# mem.net
KiCad netlist of a schematic drawn in Altium Designer
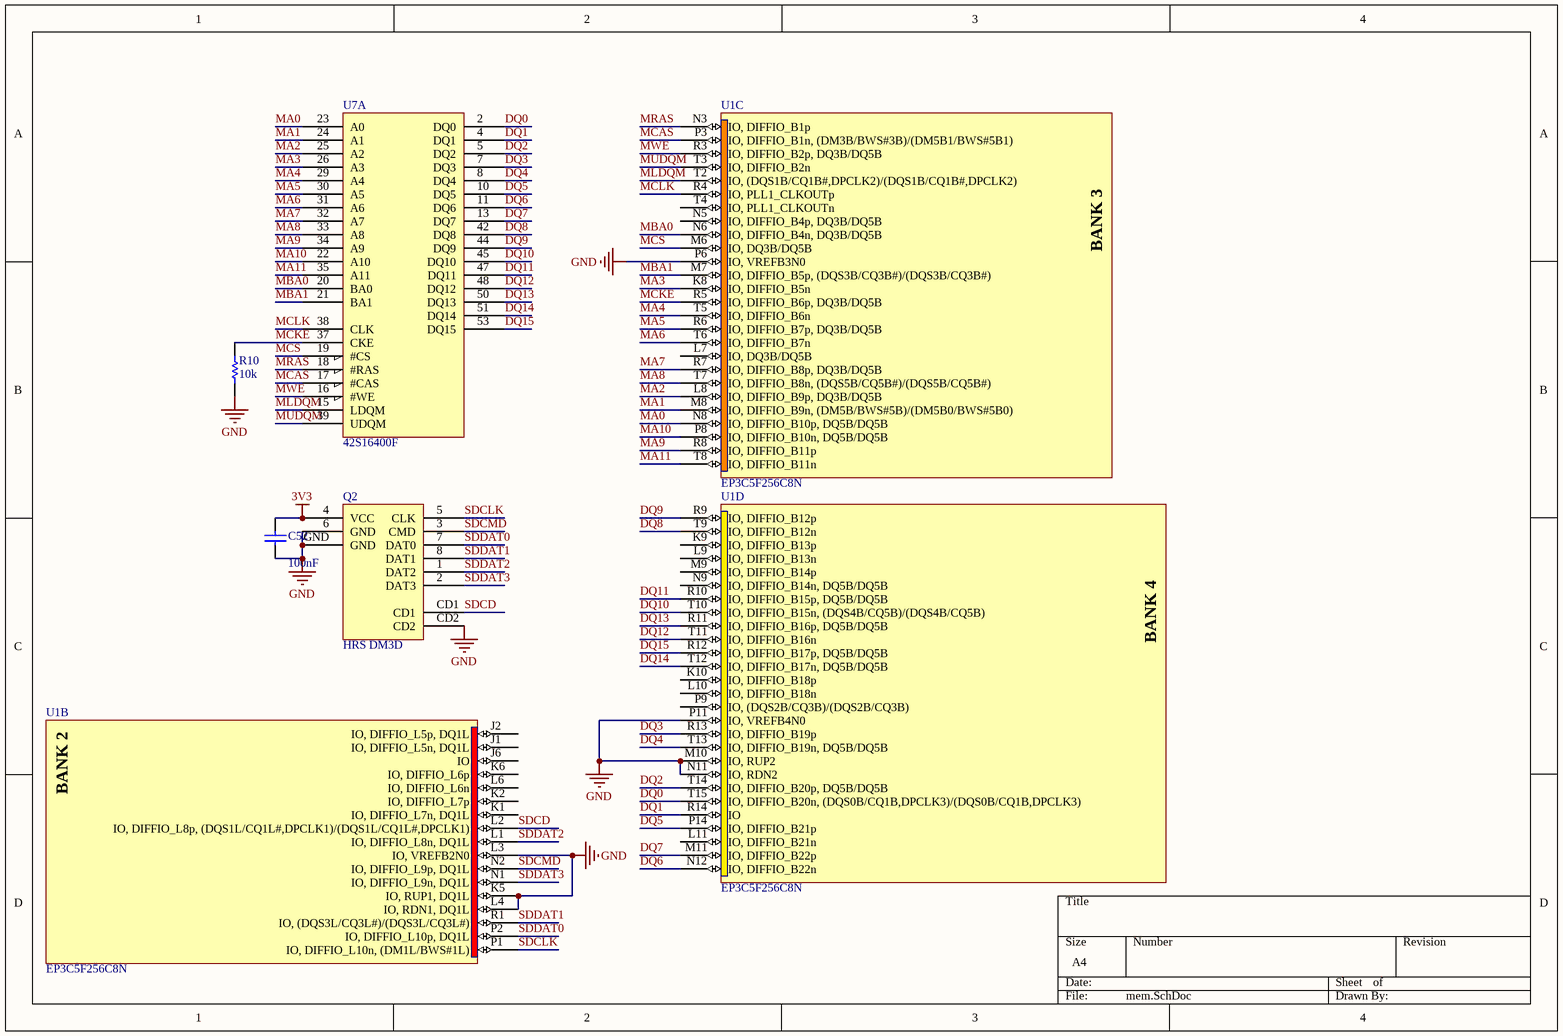
[diagram p0: mem.SchDoc]

(export (version "E")
  (design (tool "Eeschema 10.0.6"))
  (components
    (comp (ref "C52")
      (value "100nF")
      (footprint "CAPC1005X06L")
      (description "Capacitor")
      (fields (field (name "PUBLISHER") "Altium Limited"))
      (libsource (lib "Miscellaneous Devices") (part "Cap"))
    )
    (comp (ref "Q2") (value "HRS DM3D") (footprint "HRS DM3D") (libsource (lib "parts") (part "HRS DM3D")))
    (comp (ref "R10")
      (value "10k")
      (footprint "CAPC2012X135N")
      (description "Resistor")
      (fields (field (name "Comment") "Res1") (field (name "PUBLISHER") "Altium Limited"))
      (libsource (lib "Miscellaneous Devices") (part "Res1"))
    )
    (comp (ref "U1")
      (value "EP3C5F256C8N")
      (footprint "FBGA256-2")
      (fields (field (name "PUBLISHER") "Altium Limited"))
      (libsource (lib "Altera Cyclone III") (part "EP3C5F256C8N"))
    )
    (comp (ref "U7")
      (value "42S16400F")
      (footprint "54_TSOP2_400AF_N")
      (libsource (lib "parts") (part "45S16400F"))
    )
  )
  (nets
    (net (code "1") (name "/DQ0") (class "Default")
      (node (ref "U1") (pin "T15") (pinfunction "IO,_DIFFIO_B20n,_(DQS0B/CQ1B,DPCLK3)/(DQS0B/CQ1B,DPCLK3)_T15") (pintype "bidirectional"))
      (node (ref "U7") (pin "2") (pinfunction "DQ0_2") (pintype "passive"))
    )
    (net (code "2") (name "/DQ1") (class "Default")
      (node (ref "U1") (pin "R14") (pinfunction "IO_R14") (pintype "bidirectional"))
      (node (ref "U7") (pin "4") (pinfunction "DQ1_4") (pintype "passive"))
    )
    (net (code "3") (name "/DQ2") (class "Default")
      (node (ref "U1") (pin "T14") (pinfunction "IO,_DIFFIO_B20p,_DQ5B/DQ5B_T14") (pintype "bidirectional"))
      (node (ref "U7") (pin "5") (pinfunction "DQ2_5") (pintype "passive"))
    )
    (net (code "4") (name "/DQ3") (class "Default")
      (node (ref "U1") (pin "R13") (pinfunction "IO,_DIFFIO_B19p_R13") (pintype "bidirectional"))
      (node (ref "U7") (pin "7") (pinfunction "DQ3_7") (pintype "passive"))
    )
    (net (code "5") (name "/DQ4") (class "Default")
      (node (ref "U1") (pin "T13") (pinfunction "IO,_DIFFIO_B19n,_DQ5B/DQ5B_T13") (pintype "bidirectional"))
      (node (ref "U7") (pin "8") (pinfunction "DQ4_8") (pintype "passive"))
    )
    (net (code "6") (name "/DQ5") (class "Default")
      (node (ref "U1") (pin "P14") (pinfunction "IO,_DIFFIO_B21p_P14") (pintype "bidirectional"))
      (node (ref "U7") (pin "10") (pinfunction "DQ5_10") (pintype "passive"))
    )
    (net (code "7") (name "/DQ6") (class "Default")
      (node (ref "U1") (pin "N12") (pinfunction "IO,_DIFFIO_B22n_N12") (pintype "bidirectional"))
      (node (ref "U7") (pin "11") (pinfunction "DQ6_11") (pintype "passive"))
    )
    (net (code "8") (name "/DQ7") (class "Default")
      (node (ref "U1") (pin "M11") (pinfunction "IO,_DIFFIO_B22p_M11") (pintype "bidirectional"))
      (node (ref "U7") (pin "13") (pinfunction "DQ7_13") (pintype "passive"))
    )
    (net (code "9") (name "/DQ8") (class "Default")
      (node (ref "U1") (pin "T9") (pinfunction "IO,_DIFFIO_B12n_T9") (pintype "bidirectional"))
      (node (ref "U7") (pin "42") (pinfunction "DQ8_42") (pintype "passive"))
    )
    (net (code "10") (name "/DQ9") (class "Default")
      (node (ref "U1") (pin "R9") (pinfunction "IO,_DIFFIO_B12p_R9") (pintype "bidirectional"))
      (node (ref "U7") (pin "44") (pinfunction "DQ9_44") (pintype "passive"))
    )
    (net (code "11") (name "/DQ10") (class "Default")
      (node (ref "U1") (pin "T10") (pinfunction "IO,_DIFFIO_B15n,_(DQS4B/CQ5B)/(DQS4B/CQ5B)_T10") (pintype "bidirectional"))
      (node (ref "U7") (pin "45") (pinfunction "DQ10_45") (pintype "passive"))
    )
    (net (code "12") (name "/DQ11") (class "Default")
      (node (ref "U1") (pin "R10") (pinfunction "IO,_DIFFIO_B15p,_DQ5B/DQ5B_R10") (pintype "bidirectional"))
      (node (ref "U7") (pin "47") (pinfunction "DQ11_47") (pintype "passive"))
    )
    (net (code "13") (name "/DQ12") (class "Default")
      (node (ref "U1") (pin "T11") (pinfunction "IO,_DIFFIO_B16n_T11") (pintype "bidirectional"))
      (node (ref "U7") (pin "48") (pinfunction "DQ12_48") (pintype "passive"))
    )
    (net (code "14") (name "/DQ13") (class "Default")
      (node (ref "U1") (pin "R11") (pinfunction "IO,_DIFFIO_B16p,_DQ5B/DQ5B_R11") (pintype "bidirectional"))
      (node (ref "U7") (pin "50") (pinfunction "DQ13_50") (pintype "passive"))
    )
    (net (code "15") (name "/DQ14") (class "Default")
      (node (ref "U1") (pin "T12") (pinfunction "IO,_DIFFIO_B17n,_DQ5B/DQ5B_T12") (pintype "bidirectional"))
      (node (ref "U7") (pin "51") (pinfunction "DQ14_51") (pintype "passive"))
    )
    (net (code "16") (name "/DQ15") (class "Default")
      (node (ref "U1") (pin "R12") (pinfunction "IO,_DIFFIO_B17p,_DQ5B/DQ5B_R12") (pintype "bidirectional"))
      (node (ref "U7") (pin "53") (pinfunction "DQ15_53") (pintype "passive"))
    )
    (net (code "17") (name "/MA0") (class "Default")
      (node (ref "U1") (pin "N8") (pinfunction "IO,_DIFFIO_B10p,_DQ5B/DQ5B_N8") (pintype "bidirectional"))
      (node (ref "U7") (pin "23") (pinfunction "A0_23") (pintype "passive"))
    )
    (net (code "18") (name "/MA1") (class "Default")
      (node (ref "U1") (pin "M8") (pinfunction "IO,_DIFFIO_B9n,_(DM5B/BWS#5B)/(DM5B0/BWS#5B0)_M8") (pintype "bidirectional"))
      (node (ref "U7") (pin "24") (pinfunction "A1_24") (pintype "passive"))
    )
    (net (code "19") (name "/MA2") (class "Default")
      (node (ref "U1") (pin "L8") (pinfunction "IO,_DIFFIO_B9p,_DQ3B/DQ5B_L8") (pintype "bidirectional"))
      (node (ref "U7") (pin "25") (pinfunction "A2_25") (pintype "passive"))
    )
    (net (code "20") (name "/MA3") (class "Default")
      (node (ref "U1") (pin "K8") (pinfunction "IO,_DIFFIO_B5n_K8") (pintype "bidirectional"))
      (node (ref "U7") (pin "26") (pinfunction "A3_26") (pintype "passive"))
    )
    (net (code "21") (name "/MA4") (class "Default")
      (node (ref "U1") (pin "T5") (pinfunction "IO,_DIFFIO_B6n_T5") (pintype "bidirectional"))
      (node (ref "U7") (pin "29") (pinfunction "A4_29") (pintype "passive"))
    )
    (net (code "22") (name "/MA5") (class "Default")
      (node (ref "U1") (pin "R6") (pinfunction "IO,_DIFFIO_B7p,_DQ3B/DQ5B_R6") (pintype "bidirectional"))
      (node (ref "U7") (pin "30") (pinfunction "A5_30") (pintype "passive"))
    )
    (net (code "23") (name "/MA6") (class "Default")
      (node (ref "U1") (pin "T6") (pinfunction "IO,_DIFFIO_B7n_T6") (pintype "bidirectional"))
      (node (ref "U7") (pin "31") (pinfunction "A6_31") (pintype "passive"))
    )
    (net (code "24") (name "/MA7") (class "Default")
      (node (ref "U1") (pin "R7") (pinfunction "IO,_DIFFIO_B8p,_DQ3B/DQ5B_R7") (pintype "bidirectional"))
      (node (ref "U7") (pin "32") (pinfunction "A7_32") (pintype "passive"))
    )
    (net (code "25") (name "/MA8") (class "Default")
      (node (ref "U1") (pin "T7") (pinfunction "IO,_DIFFIO_B8n,_(DQS5B/CQ5B#)/(DQS5B/CQ5B#)_T7") (pintype "bidirectional"))
      (node (ref "U7") (pin "33") (pinfunction "A8_33") (pintype "passive"))
    )
    (net (code "26") (name "/MA9") (class "Default")
      (node (ref "U1") (pin "R8") (pinfunction "IO,_DIFFIO_B11p_R8") (pintype "bidirectional"))
      (node (ref "U7") (pin "34") (pinfunction "A9_34") (pintype "passive"))
    )
    (net (code "27") (name "/MA10") (class "Default")
      (node (ref "U1") (pin "P8") (pinfunction "IO,_DIFFIO_B10n,_DQ5B/DQ5B_P8") (pintype "bidirectional"))
      (node (ref "U7") (pin "22") (pinfunction "A10_22") (pintype "passive"))
    )
    (net (code "28") (name "/MA11") (class "Default")
      (node (ref "U1") (pin "T8") (pinfunction "IO,_DIFFIO_B11n_T8") (pintype "bidirectional"))
      (node (ref "U7") (pin "35") (pinfunction "A11_35") (pintype "passive"))
    )
    (net (code "29") (name "/MBA0") (class "Default")
      (node (ref "U1") (pin "N6") (pinfunction "IO,_DIFFIO_B4n,_DQ3B/DQ5B_N6") (pintype "bidirectional"))
      (node (ref "U7") (pin "20") (pinfunction "BA0_20") (pintype "passive"))
    )
    (net (code "30") (name "/MBA1") (class "Default")
      (node (ref "U1") (pin "M7") (pinfunction "IO,_DIFFIO_B5p,_(DQS3B/CQ3B#)/(DQS3B/CQ3B#)_M7") (pintype "bidirectional"))
      (node (ref "U7") (pin "21") (pinfunction "BA1_21") (pintype "passive"))
    )
    (net (code "31") (name "/MCAS") (class "Default")
      (node (ref "U1") (pin "P3") (pinfunction "IO,_DIFFIO_B1n,_(DM3B/BWS#3B)/(DM5B1/BWS#5B1)_P3") (pintype "bidirectional"))
      (node (ref "U7") (pin "17") (pinfunction "#CAS_17") (pintype "passive"))
    )
    (net (code "32") (name "/MCKE") (class "Default")
      (node (ref "R10") (pin "2") (pinfunction "2_2") (pintype "passive"))
      (node (ref "U1") (pin "R5") (pinfunction "IO,_DIFFIO_B6p,_DQ3B/DQ5B_R5") (pintype "bidirectional"))
      (node (ref "U7") (pin "37") (pinfunction "CKE_37") (pintype "passive"))
    )
    (net (code "33") (name "/MCLK") (class "Default")
      (node (ref "U1") (pin "R4") (pinfunction "IO,_PLL1_CLKOUTp_R4") (pintype "bidirectional"))
      (node (ref "U7") (pin "38") (pinfunction "CLK_38") (pintype "passive"))
    )
    (net (code "34") (name "/MCS") (class "Default")
      (node (ref "U1") (pin "M6") (pinfunction "IO,_DQ3B/DQ5B_M6") (pintype "bidirectional"))
      (node (ref "U7") (pin "19") (pinfunction "#CS_19") (pintype "passive"))
    )
    (net (code "35") (name "/MLDQM") (class "Default")
      (node (ref "U1") (pin "T2") (pinfunction "IO,_(DQS1B/CQ1B#,DPCLK2)/(DQS1B/CQ1B#,DPCLK2)_T2") (pintype "bidirectional"))
      (node (ref "U7") (pin "15") (pinfunction "LDQM_15") (pintype "passive"))
    )
    (net (code "36") (name "/MRAS") (class "Default")
      (node (ref "U1") (pin "N3") (pinfunction "IO,_DIFFIO_B1p_N3") (pintype "bidirectional"))
      (node (ref "U7") (pin "18") (pinfunction "#RAS_18") (pintype "passive"))
    )
    (net (code "37") (name "/MUDQM") (class "Default")
      (node (ref "U1") (pin "T3") (pinfunction "IO,_DIFFIO_B2n_T3") (pintype "bidirectional"))
      (node (ref "U7") (pin "39") (pinfunction "UDQM_39") (pintype "passive"))
    )
    (net (code "38") (name "/MWE") (class "Default")
      (node (ref "U1") (pin "R3") (pinfunction "IO,_DIFFIO_B2p,_DQ3B/DQ5B_R3") (pintype "bidirectional"))
      (node (ref "U7") (pin "16") (pinfunction "#WE_16") (pintype "passive"))
    )
    (net (code "39") (name "/SDCD") (class "Default")
      (node (ref "Q2") (pin "CD1") (pinfunction "CD1_CD1") (pintype "passive"))
      (node (ref "U1") (pin "L2") (pinfunction "IO,_DIFFIO_L8p,_(DQS1L/CQ1L#,DPCLK1)/(DQS1L/CQ1L#,DPCLK1)_L2") (pintype "bidirectional"))
    )
    (net (code "40") (name "/SDCLK") (class "Default")
      (node (ref "Q2") (pin "5") (pinfunction "CLK_5") (pintype "passive"))
      (node (ref "U1") (pin "P1") (pinfunction "IO,_DIFFIO_L10n,_(DM1L/BWS#1L)_P1") (pintype "bidirectional"))
    )
    (net (code "41") (name "/SDCMD") (class "Default")
      (node (ref "Q2") (pin "3") (pinfunction "CMD_3") (pintype "passive"))
      (node (ref "U1") (pin "N2") (pinfunction "IO,_DIFFIO_L9p,_DQ1L_N2") (pintype "bidirectional"))
    )
    (net (code "42") (name "/SDDAT0") (class "Default")
      (node (ref "Q2") (pin "7") (pinfunction "DAT0_7") (pintype "passive"))
      (node (ref "U1") (pin "P2") (pinfunction "IO,_DIFFIO_L10p,_DQ1L_P2") (pintype "bidirectional"))
    )
    (net (code "43") (name "/SDDAT1") (class "Default")
      (node (ref "Q2") (pin "8") (pinfunction "DAT1_8") (pintype "passive"))
      (node (ref "U1") (pin "R1") (pinfunction "IO,_(DQS3L/CQ3L#)/(DQS3L/CQ3L#)_R1") (pintype "bidirectional"))
    )
    (net (code "44") (name "/SDDAT2") (class "Default")
      (node (ref "Q2") (pin "1") (pinfunction "DAT2_1") (pintype "passive"))
      (node (ref "U1") (pin "L1") (pinfunction "IO,_DIFFIO_L8n,_DQ1L_L1") (pintype "bidirectional"))
    )
    (net (code "45") (name "/SDDAT3") (class "Default")
      (node (ref "Q2") (pin "2") (pinfunction "DAT3_2") (pintype "passive"))
      (node (ref "U1") (pin "N1") (pinfunction "IO,_DIFFIO_L9n,_DQ1L_N1") (pintype "bidirectional"))
    )
    (net (code "46") (name "3V3") (class "Default")
      (node (ref "C52") (pin "2") (pinfunction "2_2") (pintype "passive"))
      (node (ref "Q2") (pin "4") (pinfunction "VCC_4") (pintype "passive"))
    )
    (net (code "47") (name "GND") (class "Default")
      (node (ref "C52") (pin "1") (pinfunction "1_1") (pintype "passive"))
      (node (ref "Q2") (pin "6") (pinfunction "GND_6") (pintype "passive"))
      (node (ref "Q2") (pin "CD2") (pinfunction "CD2_CD2") (pintype "passive"))
      (node (ref "Q2") (pin "GND") (pinfunction "GND_GND") (pintype "passive"))
      (node (ref "R10") (pin "1") (pinfunction "1_1") (pintype "passive"))
      (node (ref "U1") (pin "K5") (pinfunction "IO,_RUP1,_DQ1L_K5") (pintype "bidirectional"))
      (node (ref "U1") (pin "L3") (pinfunction "IO,_VREFB2N0_L3") (pintype "bidirectional"))
      (node (ref "U1") (pin "L4") (pinfunction "IO,_RDN1,_DQ1L_L4") (pintype "bidirectional"))
      (node (ref "U1") (pin "M10") (pinfunction "IO,_RUP2_M10") (pintype "bidirectional"))
      (node (ref "U1") (pin "N11") (pinfunction "IO,_RDN2_N11") (pintype "bidirectional"))
      (node (ref "U1") (pin "P11") (pinfunction "IO,_VREFB4N0_P11") (pintype "bidirectional"))
      (node (ref "U1") (pin "P6") (pinfunction "IO,_VREFB3N0_P6") (pintype "bidirectional"))
    )
    (net (code "48") (name "unconnected-(U1B-IO,_DIFFIO_L5n,_DQ1L-PadJ1)") (class "Default")
      (node (ref "U1") (pin "J1") (pinfunction "IO,_DIFFIO_L5n,_DQ1L_J1") (pintype "bidirectional"))
    )
    (net (code "49") (name "unconnected-(U1B-IO,_DIFFIO_L5p,_DQ1L-PadJ2)") (class "Default")
      (node (ref "U1") (pin "J2") (pinfunction "IO,_DIFFIO_L5p,_DQ1L_J2") (pintype "bidirectional"))
    )
    (net (code "50") (name "unconnected-(U1B-IO,_DIFFIO_L6n-PadL6)") (class "Default")
      (node (ref "U1") (pin "L6") (pinfunction "IO,_DIFFIO_L6n_L6") (pintype "bidirectional"))
    )
    (net (code "51") (name "unconnected-(U1B-IO,_DIFFIO_L6p-PadK6)") (class "Default")
      (node (ref "U1") (pin "K6") (pinfunction "IO,_DIFFIO_L6p_K6") (pintype "bidirectional"))
    )
    (net (code "52") (name "unconnected-(U1B-IO,_DIFFIO_L7n,_DQ1L-PadK1)") (class "Default")
      (node (ref "U1") (pin "K1") (pinfunction "IO,_DIFFIO_L7n,_DQ1L_K1") (pintype "bidirectional"))
    )
    (net (code "53") (name "unconnected-(U1B-IO,_DIFFIO_L7p-PadK2)") (class "Default")
      (node (ref "U1") (pin "K2") (pinfunction "IO,_DIFFIO_L7p_K2") (pintype "bidirectional"))
    )
    (net (code "54") (name "unconnected-(U1B-IO-PadJ6)") (class "Default")
      (node (ref "U1") (pin "J6") (pinfunction "IO_J6") (pintype "bidirectional"))
    )
    (net (code "55") (name "unconnected-(U1C-IO,_DIFFIO_B4p,_DQ3B{slash}DQ5B-PadN5)") (class "Default")
      (node (ref "U1") (pin "N5") (pinfunction "IO,_DIFFIO_B4p,_DQ3B/DQ5B_N5") (pintype "bidirectional"))
    )
    (net (code "56") (name "unconnected-(U1C-IO,_DQ3B{slash}DQ5B-PadL7)") (class "Default")
      (node (ref "U1") (pin "L7") (pinfunction "IO,_DQ3B/DQ5B_L7") (pintype "bidirectional"))
    )
    (net (code "57") (name "unconnected-(U1C-IO,_PLL1_CLKOUTn-PadT4)") (class "Default")
      (node (ref "U1") (pin "T4") (pinfunction "IO,_PLL1_CLKOUTn_T4") (pintype "bidirectional"))
    )
    (net (code "58") (name "unconnected-(U1D-IO,_(DQS2B{slash}CQ3B){slash}(DQS2B{slash}CQ3B)-PadP9)") (class "Default")
      (node (ref "U1") (pin "P9") (pinfunction "IO,_(DQS2B/CQ3B)/(DQS2B/CQ3B)_P9") (pintype "bidirectional"))
    )
    (net (code "59") (name "unconnected-(U1D-IO,_DIFFIO_B13n-PadL9)") (class "Default")
      (node (ref "U1") (pin "L9") (pinfunction "IO,_DIFFIO_B13n_L9") (pintype "bidirectional"))
    )
    (net (code "60") (name "unconnected-(U1D-IO,_DIFFIO_B13p-PadK9)") (class "Default")
      (node (ref "U1") (pin "K9") (pinfunction "IO,_DIFFIO_B13p_K9") (pintype "bidirectional"))
    )
    (net (code "61") (name "unconnected-(U1D-IO,_DIFFIO_B14n,_DQ5B{slash}DQ5B-PadN9)") (class "Default")
      (node (ref "U1") (pin "N9") (pinfunction "IO,_DIFFIO_B14n,_DQ5B/DQ5B_N9") (pintype "bidirectional"))
    )
    (net (code "62") (name "unconnected-(U1D-IO,_DIFFIO_B14p-PadM9)") (class "Default")
      (node (ref "U1") (pin "M9") (pinfunction "IO,_DIFFIO_B14p_M9") (pintype "bidirectional"))
    )
    (net (code "63") (name "unconnected-(U1D-IO,_DIFFIO_B18n-PadL10)") (class "Default")
      (node (ref "U1") (pin "L10") (pinfunction "IO,_DIFFIO_B18n_L10") (pintype "bidirectional"))
    )
    (net (code "64") (name "unconnected-(U1D-IO,_DIFFIO_B18p-PadK10)") (class "Default")
      (node (ref "U1") (pin "K10") (pinfunction "IO,_DIFFIO_B18p_K10") (pintype "bidirectional"))
    )
    (net (code "65") (name "unconnected-(U1D-IO,_DIFFIO_B21n-PadL11)") (class "Default")
      (node (ref "U1") (pin "L11") (pinfunction "IO,_DIFFIO_B21n_L11") (pintype "bidirectional"))
    )
  )
)
